# RPI.net
KiCad netlist of a schematic drawn in Altium Designer
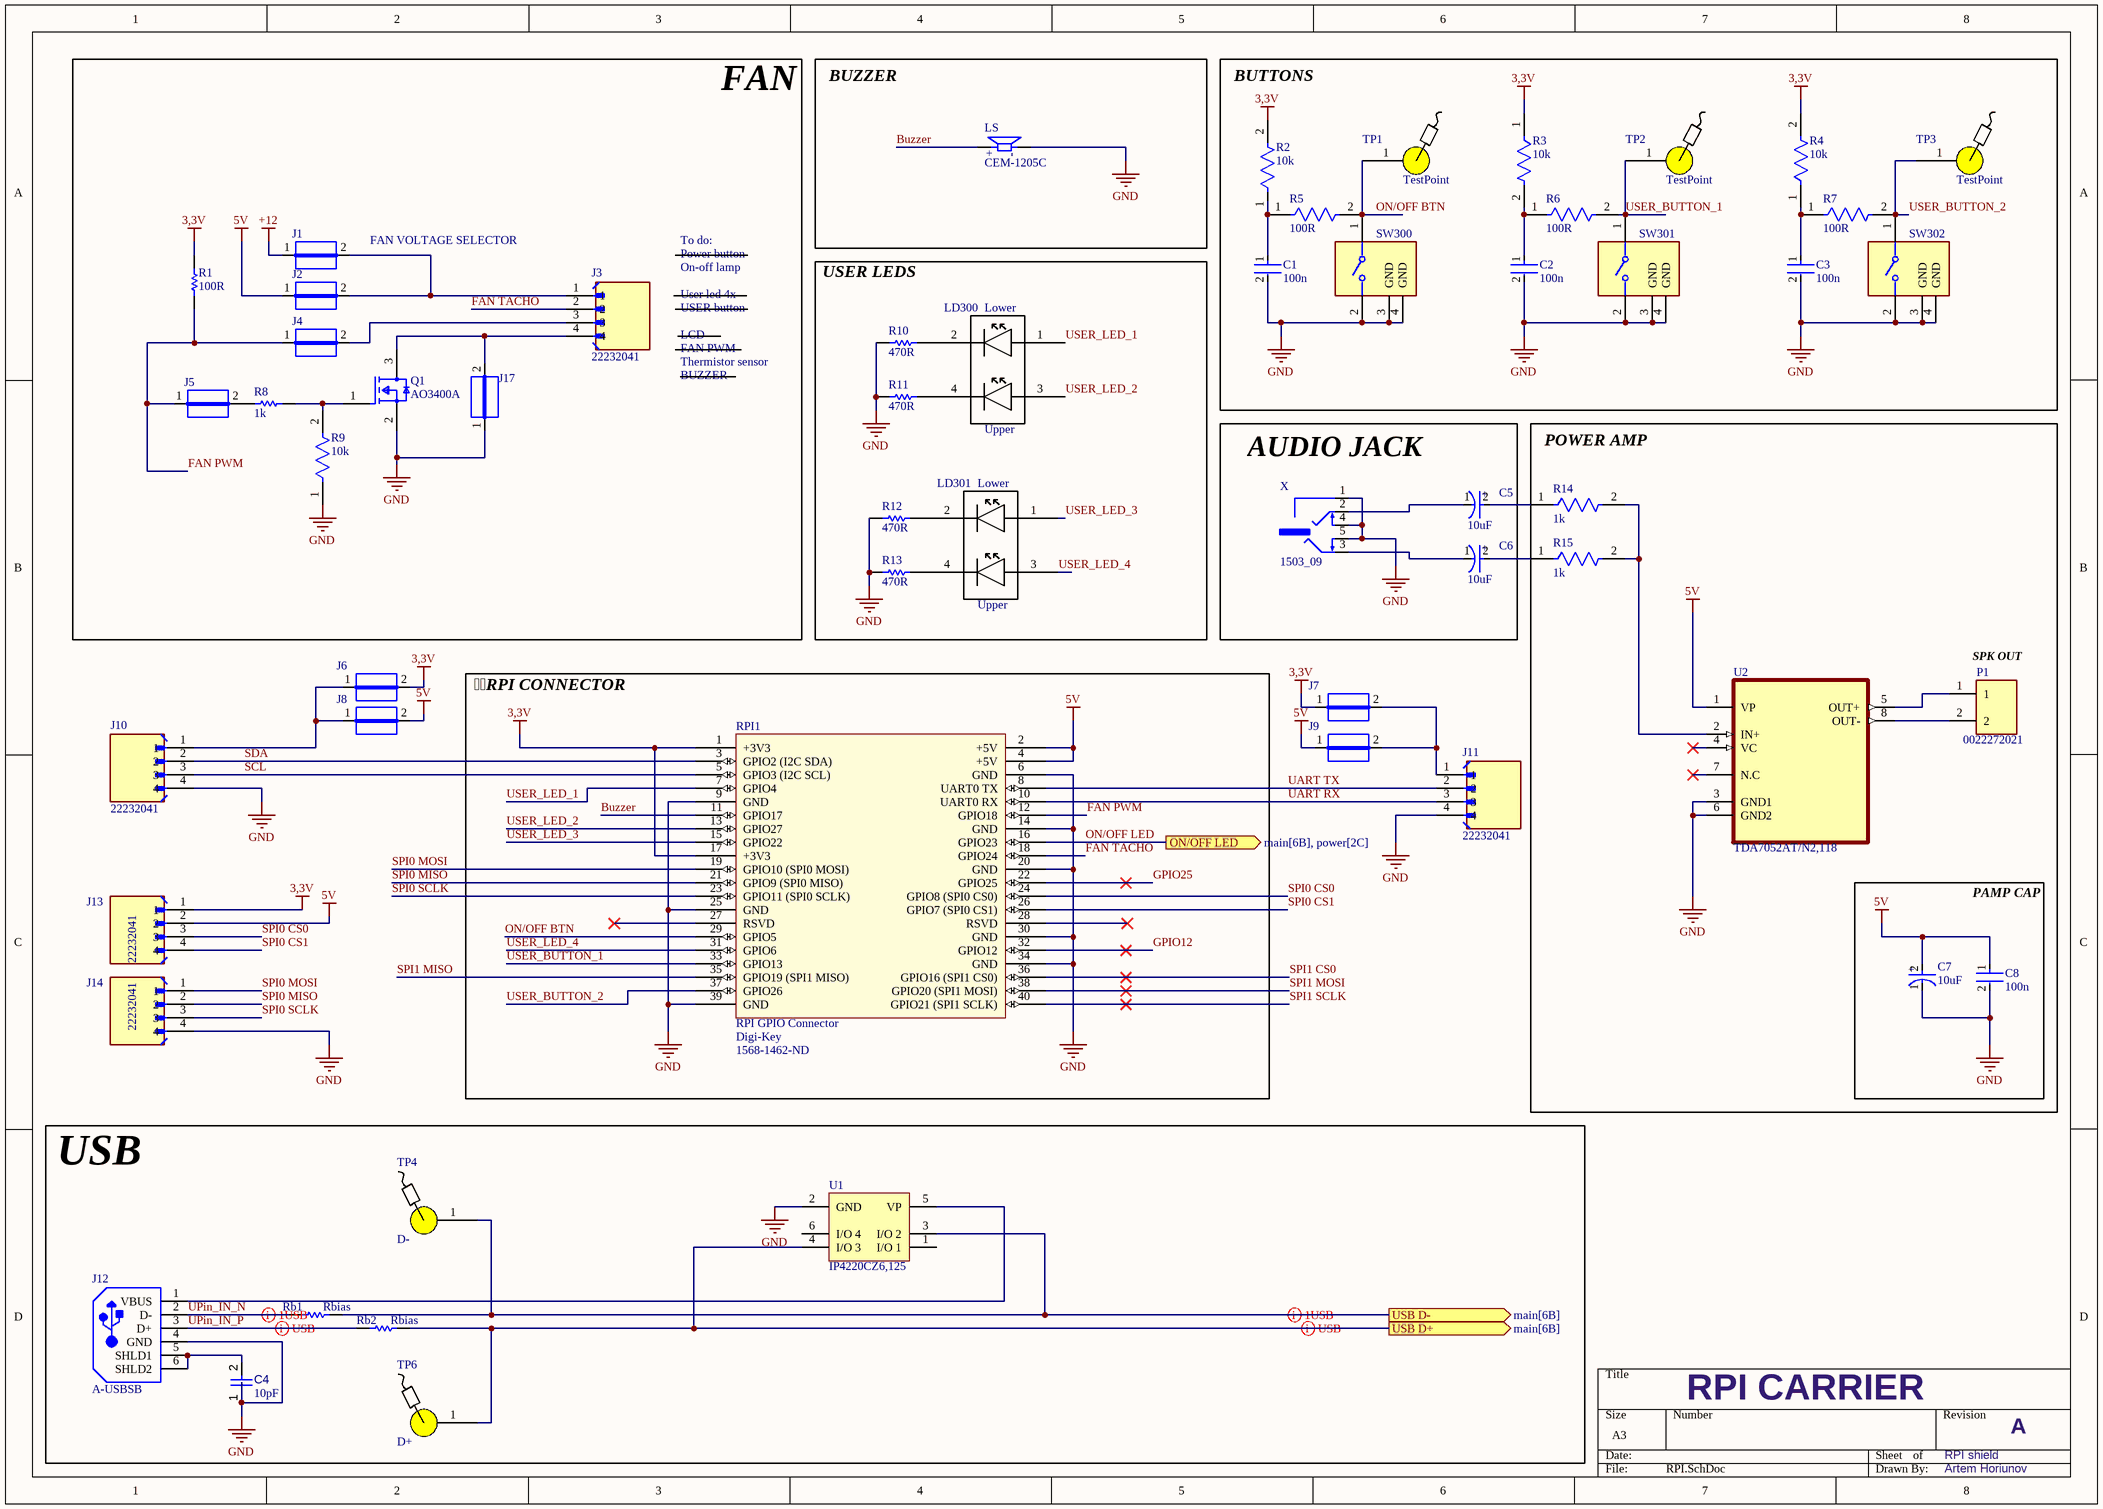
[diagram p0: RPI.SchDoc]

(export (version "E")
  (design (tool "Eeschema 10.0.6"))
  (components
    (comp (ref "C1")
      (value "100n")
      (footprint "FP-C0603C-CF-MFG")
      (description "CAP CER 0.1UF 50V X7R 0603")
      (fields (field (name "TOLERANCE") "0.1") (field (name "MANUFACTURER") "KEMET"))
      (libsource (lib "Altium Content Vault") (part "b4654b650e69147ec39a6b967a45e02"))
    )
    (comp (ref "C2")
      (value "100n")
      (footprint "FP-C0603C-CF-MFG")
      (description "CAP CER 0.1UF 50V X7R 0603")
      (fields (field (name "TOLERANCE") "0.1") (field (name "MANUFACTURER") "KEMET"))
      (libsource (lib "Altium Content Vault") (part "b4654b650e69147ec39a6b967a45e02"))
    )
    (comp (ref "C3")
      (value "100n")
      (footprint "FP-C0603C-CF-MFG")
      (description "CAP CER 0.1UF 50V X7R 0603")
      (fields (field (name "TOLERANCE") "0.1") (field (name "MANUFACTURER") "KEMET"))
      (libsource (lib "Altium Content Vault") (part "b4654b650e69147ec39a6b967a45e02"))
    )
    (comp (ref "C4")
      (value "10pF")
      (footprint "CAPC1005X55X30LL05T10")
      (description "Chip Capacitor, 10 pF, +/- 0.25 pF, 50 V, 0402 (1005 Metric)")
      (fields
        (field (name "TOLERANCE") "0.25%")
        (field (name "Comment") "Capacitor 10 pF +/- 0.25 pF 50 V 0402")
      )
      (libsource (lib "WUST") (part "CAP-NP-2"))
    )
    (comp (ref "C5")
      (value "10uF")
      (footprint "FP-SC-MFG")
      (description "CAP ALUM 10UF 20% 35V SMD")
      (fields (field (name "TOLERANCE") "20%") (field (name "VOLTAGE") "35V"))
      (libsource (lib "Altium Content Vault") (part "203bc49f2ac43e59fd269a8c329ed05"))
    )
    (comp (ref "C6")
      (value "10uF")
      (footprint "FP-SC-MFG")
      (description "CAP ALUM 10UF 20% 35V SMD")
      (fields (field (name "TOLERANCE") "20%") (field (name "VOLTAGE") "35V"))
      (libsource (lib "Altium Content Vault") (part "203bc49f2ac43e59fd269a8c329ed05"))
    )
    (comp (ref "C7")
      (value "10uF")
      (footprint "FP-SC-MFG")
      (description "CAP ALUM 10UF 20% 35V SMD")
      (fields (field (name "TOLERANCE") "20%") (field (name "VOLTAGE") "35V"))
      (libsource (lib "Altium Content Vault") (part "203bc49f2ac43e59fd269a8c329ed05"))
    )
    (comp (ref "C8")
      (value "100n")
      (footprint "FP-C0603C-CF-MFG")
      (description "CAP CER 0.1UF 50V X7R 0603")
      (fields (field (name "TOLERANCE") "0.1") (field (name "MANUFACTURER") "KEMET"))
      (libsource (lib "Altium Content Vault") (part "b4654b650e69147ec39a6b967a45e02"))
    )
    (comp (ref "J1") (value "JUMPER") (footprint "JUMPER") (libsource (lib "") (part "JUMPER_1")))
    (comp (ref "J2") (value "JUMPER") (footprint "JUMPER") (libsource (lib "") (part "JUMPER_1")))
    (comp (ref "J3")
      (value "22232041")
      (footprint "MOLEX_22232041")
      (description "Conn Wire to Board HDR 4 POS 2.54mm Solder ST Top Entry Thru-Hole KKÂ® Bag")
      (fields (field (name "MF") "Molex"))
      (libsource (lib "22232041") (part "22232041"))
    )
    (comp (ref "J4") (value "JUMPER") (footprint "JUMPER") (libsource (lib "") (part "JUMPER_1")))
    (comp (ref "J5") (value "JUMPER") (footprint "JUMPER") (libsource (lib "") (part "JUMPER_1")))
    (comp (ref "J6") (value "JUMPER") (footprint "JUMPER") (libsource (lib "") (part "JUMPER_1")))
    (comp (ref "J7") (value "JUMPER") (footprint "JUMPER") (libsource (lib "") (part "JUMPER_1")))
    (comp (ref "J8") (value "JUMPER") (footprint "JUMPER") (libsource (lib "") (part "JUMPER_1")))
    (comp (ref "J9") (value "JUMPER") (footprint "JUMPER") (libsource (lib "") (part "JUMPER_1")))
    (comp (ref "J10")
      (value "22232041")
      (footprint "MOLEX_22232041")
      (description "Conn Wire to Board HDR 4 POS 2.54mm Solder ST Top Entry Thru-Hole KKÂ® Bag")
      (fields (field (name "MF") "Molex"))
      (libsource (lib "") (part "22232041_1"))
    )
    (comp (ref "J11")
      (value "22232041")
      (footprint "MOLEX_22232041")
      (description "Conn Wire to Board HDR 4 POS 2.54mm Solder ST Top Entry Thru-Hole KKÂ® Bag")
      (fields (field (name "MF") "Molex"))
      (libsource (lib "22232041") (part "22232041"))
    )
    (comp (ref "J12")
      (value "A-USBSB")
      (footprint "ASSM-A-USBSB-4_V")
      (description "Connector Receptacle, USB Type B, Right Angle, -20 to 85 degC, 4-Pin THD, RoHS, Tray")
      (fields (field (name "MANUFACTURER") "ASSMANN WSW"))
      (libsource (lib "Altium Content Vault") (part "USB-4-2SHLD"))
    )
    (comp (ref "J13")
      (value "22232041")
      (footprint "MOLEX_22232041")
      (description "Conn Wire to Board HDR 4 POS 2.54mm Solder ST Top Entry Thru-Hole KKÂ® Bag")
      (fields (field (name "MF") "Molex"))
      (libsource (lib "") (part "22232041_2"))
    )
    (comp (ref "J14")
      (value "22232041")
      (footprint "MOLEX_22232041")
      (description "Conn Wire to Board HDR 4 POS 2.54mm Solder ST Top Entry Thru-Hole KKÂ® Bag")
      (fields (field (name "MF") "Molex"))
      (libsource (lib "") (part "22232041_2"))
    )
    (comp (ref "J17") (value "JUMPER") (footprint "JUMPER") (libsource (lib "WUST") (part "JUMPER")))
    (comp (ref "LD300")
      (value "~")
      (footprint "LedHolder:LED_HOLDER")
      (libsource (lib "LedHolder") (part "DoubleStack_Side_Led_3mm"))
    )
    (comp (ref "LD301")
      (value "~")
      (footprint "LedHolder:LED_HOLDER")
      (libsource (lib "LedHolder") (part "DoubleStack_Side_Led_3mm"))
    )
    (comp (ref "LS")
      (value "CEM-1205C")
      (footprint "CUI_CEM-1205C")
      (description "12 mm, 5 V, 85 dB, Through Hole, Sealed, Driving Circuit, Magnetic Audio Indicator Buzzer")
      (fields (field (name "MF") "CUI Devices"))
      (libsource (lib "CEM-1205C") (part "CEM-1205C"))
    )
    (comp (ref "P1")
      (value "0022272021")
      (footprint "MOLEX_0022272021")
      (description "Connector Header Through Hole 2 position 0.100 (2.54mm)")
      (fields (field (name "MF") "Molex"))
      (libsource (lib "0022272021") (part "0022272021"))
    )
    (comp (ref "Q1")
      (value "AO3400A")
      (footprint "FP-SOT23-MFG")
      (description "MOSFET N-CH 30V 5.7A SOT23")
      (libsource (lib "Altium Content Vault") (part "0a9ea7c96deaaede766a5b531c28de0"))
    )
    (comp (ref "R1")
      (value "100R")
      (footprint "RESC0603(1608)_N")
      (description "0.1W 1% 0603 (1608 Metric)  SMD")
      (fields (field (name "TOLERANCE") "5 %") (field (name "POWER") "0.1 W"))
      (libsource (lib "Altium Content Vault") (part "RES"))
    )
    (comp (ref "R2")
      (value "10k")
      (footprint "FP-RC0603-0_55-IPC_C")
      (description "RES 10K OHM 1% 1/10W 0603")
      (fields (field (name "TOLERANCE") "1%"))
      (libsource (lib "Altium Content Vault") (part "1029c3af85768c4190bb7ad29bc67b5"))
    )
    (comp (ref "R3")
      (value "10k")
      (footprint "FP-RC0603-0_55-IPC_C")
      (description "RES 10K OHM 1% 1/10W 0603")
      (fields (field (name "TOLERANCE") "1%"))
      (libsource (lib "Altium Content Vault") (part "1029c3af85768c4190bb7ad29bc67b5"))
    )
    (comp (ref "R4")
      (value "10k")
      (footprint "FP-RC0603-0_55-IPC_C")
      (description "RES 10K OHM 1% 1/10W 0603")
      (fields (field (name "TOLERANCE") "1%"))
      (libsource (lib "Altium Content Vault") (part "1029c3af85768c4190bb7ad29bc67b5"))
    )
    (comp (ref "R5")
      (value "100R")
      (footprint "FP-RC0603-0_55-MFG")
      (fields (field (name "TOLERANCE") "1%"))
      (libsource (lib "Altium Content Vault") (part "1029c3af85768c4190bb7ad29bc67b5"))
    )
    (comp (ref "R6")
      (value "100R")
      (footprint "FP-RC0603-0_55-MFG")
      (fields (field (name "TOLERANCE") "1%"))
      (libsource (lib "Altium Content Vault") (part "1029c3af85768c4190bb7ad29bc67b5"))
    )
    (comp (ref "R7")
      (value "100R")
      (footprint "FP-RC0603-0_55-MFG")
      (fields (field (name "TOLERANCE") "1%"))
      (libsource (lib "Altium Content Vault") (part "1029c3af85768c4190bb7ad29bc67b5"))
    )
    (comp (ref "R8")
      (value "1k")
      (footprint "RESC0603(1608)_N")
      (description "0.1W 5% 0603 (1608 Metric)  SMD")
      (fields (field (name "TOLERANCE") "5 %") (field (name "POWER") "0.1 W"))
      (libsource (lib "Altium Content Vault") (part "RES"))
    )
    (comp (ref "R9")
      (value "10k")
      (footprint "FP-RC0603-0_55-IPC_C")
      (description "RES 10K OHM 1% 1/10W 0603")
      (fields (field (name "TOLERANCE") "1%"))
      (libsource (lib "Altium Content Vault") (part "1029c3af85768c4190bb7ad29bc67b5"))
    )
    (comp (ref "R10")
      (value "470R")
      (footprint "RESC1608X55X25LL10T15")
      (libsource (lib "Altium Content Vault") (part "RES-2"))
    )
    (comp (ref "R11")
      (value "470R")
      (footprint "RESC1608X55X25LL10T15")
      (libsource (lib "Altium Content Vault") (part "RES-2"))
    )
    (comp (ref "R12")
      (value "470R")
      (footprint "RESC1608X55X25LL10T15")
      (libsource (lib "Altium Content Vault") (part "RES-2"))
    )
    (comp (ref "R13")
      (value "470R")
      (footprint "RESC1608X55X25LL10T15")
      (libsource (lib "Altium Content Vault") (part "RES-2"))
    )
    (comp (ref "R14")
      (value "1k")
      (footprint "FP-ERA3A-IPC_C")
      (description "RES SMD 1K OHM 0.1% 1/10W 0603")
      (fields (field (name "TOLERANCE") "0.1%"))
      (libsource (lib "Altium Content Vault") (part "1029c3af85768c4190bb7ad29bc67b5"))
    )
    (comp (ref "R15")
      (value "1k")
      (footprint "FP-ERA3A-IPC_C")
      (description "RES SMD 1K OHM 0.1% 1/10W 0603")
      (fields (field (name "TOLERANCE") "0.1%"))
      (libsource (lib "Altium Content Vault") (part "1029c3af85768c4190bb7ad29bc67b5"))
    )
    (comp (ref "Rb1")
      (value "Rbias")
      (footprint "RESC1005X40X25NL05T05")
      (fields (field (name "PART NUMBER") "CRCW040210R0FKED") (field (name "MANUFACTURER") "Vishay Dale"))
      (libsource (lib "Altium Content Vault") (part "RES"))
    )
    (comp (ref "Rb2")
      (value "Rbias")
      (footprint "RESC1005X40X25NL05T05")
      (fields (field (name "PART NUMBER") "CRCW040210R0FKED") (field (name "MANUFACTURER") "Vishay Dale"))
      (libsource (lib "Altium Content Vault") (part "RES"))
    )
    (comp (ref "RPI1")
      (value "RPI GPIO Connector")
      (footprint "rpi")
      (description "GPIO Header for Raspberry Pi A+/B+/Pi 2/Pi 3 - 2x20")
      (fields
        (field (name "MANUFACTURER") "SparkFun Electronics")
        (field (name "MANUFACTURER PART NUMBER") "PRT-14017")
        (field (name "SUPPLIER 1") "Digi-Key")
        (field (name "SUPPLIER PART NUMBER 1") "1568-1462-ND")
      )
      (libsource (lib "rpi") (part "rpi connector"))
    )
    (comp (ref "SW300")
      (value "B3F-3122")
      (footprint "FP-B3F-3122-MFG")
      (description "SWITCH TACTILE SPST-NO 0.05A 24V")
      (libsource (lib "Altium Content Vault") (part "05c531d4b500f7e9514fa3f65f375ae"))
    )
    (comp (ref "SW301")
      (value "B3F-3122")
      (footprint "FP-B3F-3122-MFG")
      (description "SWITCH TACTILE SPST-NO 0.05A 24V")
      (libsource (lib "Altium Content Vault") (part "05c531d4b500f7e9514fa3f65f375ae"))
    )
    (comp (ref "SW302")
      (value "B3F-3122")
      (footprint "FP-B3F-3122-MFG")
      (description "SWITCH TACTILE SPST-NO 0.05A 24V")
      (libsource (lib "Altium Content Vault") (part "05c531d4b500f7e9514fa3f65f375ae"))
    )
    (comp (ref "TP1")
      (value "TestPoint")
      (footprint "TestPoint")
      (libsource (lib "TestPoint") (part "TestPoint"))
    )
    (comp (ref "TP2")
      (value "TestPoint")
      (footprint "TestPoint")
      (libsource (lib "TestPoint") (part "TestPoint"))
    )
    (comp (ref "TP3")
      (value "TestPoint")
      (footprint "TestPoint")
      (libsource (lib "TestPoint") (part "TestPoint"))
    )
    (comp (ref "TP4") (value "D-") (footprint "TestPoint") (libsource (lib "TestPoint") (part "TestPoint")))
    (comp (ref "TP6") (value "D+") (footprint "TestPoint") (libsource (lib "TestPoint") (part "TestPoint")))
    (comp (ref "U1")
      (value "IP4220CZ6,125")
      (footprint "NXP-SOT457_L")
      (fields (field (name "PARTNUMBER") "IP4220CZ6") (field (name "MANUFACTURER") "NXP Semiconductors"))
      (libsource (lib "Altium Content Vault") (part "NXP-IP4220CZ6-6"))
    )
    (comp (ref "U2")
      (value "TDA7052AT/N2,118")
      (footprint "SOIC127P600X175-8N")
      (description "1 W BTL mono audio amplifier with DC volume control")
      (libsource (lib "TDA7052AT_N2_118") (part "TDA7052AT/N2,118"))
    )
    (comp (ref "X")
      (value "1503_09")
      (footprint "1503_09")
      (description "1503 - Lumberg 3.5mm Right Angle Jack Chassis Socket")
      (fields (field (name "MP") "1503 09") (field (name "MF") "NEC"))
      (libsource (lib "1503_09") (part "1503_09"))
    )
  )
  (nets
    (net (code "1") (name "+12") (class "Default")
      (node (ref "J1") (pin "1") (pinfunction "1_1") (pintype "passive"))
    )
    (net (code "2") (name "/Buzzer") (class "Default")
      (node (ref "LS") (pin "P") (pinfunction "P_P") (pintype "passive"))
      (node (ref "RPI1") (pin "11") (pinfunction "GPIO17_11") (pintype "bidirectional"))
    )
    (net (code "3") (name "/FAN PWM") (class "Default")
      (node (ref "J4") (pin "1") (pinfunction "1_1") (pintype "passive"))
      (node (ref "J5") (pin "1") (pinfunction "1_1") (pintype "passive"))
      (node (ref "R1") (pin "1") (pinfunction "1_1") (pintype "passive"))
      (node (ref "RPI1") (pin "12") (pinfunction "GPIO18_12") (pintype "bidirectional"))
    )
    (net (code "4") (name "/FAN TACHO") (class "Default")
      (node (ref "J3") (pin "2") (pinfunction "2_2") (pintype "passive"))
      (node (ref "RPI1") (pin "18") (pinfunction "GPIO24_18") (pintype "bidirectional"))
    )
    (net (code "5") (name "/GPIO12") (class "Default")
      (node (ref "RPI1") (pin "32") (pinfunction "GPIO12_32") (pintype "bidirectional"))
    )
    (net (code "6") (name "/GPIO25") (class "Default")
      (node (ref "RPI1") (pin "22") (pinfunction "GPIO25_22") (pintype "bidirectional"))
    )
    (net (code "7") (name "/ON{slash}OFF BTN") (class "Default")
      (node (ref "R5") (pin "2") (pinfunction "2_2") (pintype "passive"))
      (node (ref "RPI1") (pin "29") (pinfunction "GPIO5_29") (pintype "bidirectional"))
      (node (ref "SW300") (pin "1") (pinfunction "1_1") (pintype "passive"))
      (node (ref "TP1") (pin "1") (pintype "passive"))
    )
    (net (code "8") (name "/ON{slash}OFF LED") (class "Default")
      (node (ref "RPI1") (pin "16") (pinfunction "GPIO23_16") (pintype "bidirectional"))
    )
    (net (code "9") (name "/SCL") (class "Default")
      (node (ref "J10") (pin "3") (pinfunction "3_3") (pintype "passive"))
      (node (ref "RPI1") (pin "5") (pinfunction "GPIO3_(I2C_SCL)_5") (pintype "bidirectional"))
    )
    (net (code "10") (name "/SDA") (class "Default")
      (node (ref "J10") (pin "2") (pinfunction "2_2") (pintype "passive"))
      (node (ref "RPI1") (pin "3") (pinfunction "GPIO2_(I2C_SDA)_3") (pintype "bidirectional"))
    )
    (net (code "11") (name "/SPI0 CS0") (class "Default")
      (node (ref "J13") (pin "3") (pinfunction "3_3") (pintype "passive"))
      (node (ref "RPI1") (pin "24") (pinfunction "GPIO8_(SPI0_CS0)_24") (pintype "bidirectional"))
    )
    (net (code "12") (name "/SPI0 CS1") (class "Default")
      (node (ref "J13") (pin "4") (pinfunction "4_4") (pintype "passive"))
      (node (ref "RPI1") (pin "26") (pinfunction "GPIO7_(SPI0_CS1)_26") (pintype "bidirectional"))
    )
    (net (code "13") (name "/SPI0 MISO") (class "Default")
      (node (ref "J14") (pin "2") (pinfunction "2_2") (pintype "passive"))
      (node (ref "RPI1") (pin "21") (pinfunction "GPIO9_(SPI0_MISO)_21") (pintype "bidirectional"))
    )
    (net (code "14") (name "/SPI0 MOSI") (class "Default")
      (node (ref "J14") (pin "1") (pinfunction "1_1") (pintype "passive"))
      (node (ref "RPI1") (pin "19") (pinfunction "GPIO10_(SPI0_MOSI)_19") (pintype "bidirectional"))
    )
    (net (code "15") (name "/SPI0 SCLK") (class "Default")
      (node (ref "J14") (pin "3") (pinfunction "3_3") (pintype "passive"))
      (node (ref "RPI1") (pin "23") (pinfunction "GPIO11_(SPI0_SCLK)_23") (pintype "bidirectional"))
    )
    (net (code "16") (name "/SPI1 CS0") (class "Default")
      (node (ref "RPI1") (pin "36") (pinfunction "GPIO16_(SPI1_CS0)_36") (pintype "bidirectional"))
    )
    (net (code "17") (name "/SPI1 MISO") (class "Default")
      (node (ref "RPI1") (pin "35") (pinfunction "GPIO19_(SPI1_MISO)_35") (pintype "bidirectional"))
    )
    (net (code "18") (name "/SPI1 MOSI") (class "Default")
      (node (ref "RPI1") (pin "38") (pinfunction "GPIO20_(SPI1_MOSI)_38") (pintype "bidirectional"))
    )
    (net (code "19") (name "/SPI1 SCLK") (class "Default")
      (node (ref "RPI1") (pin "40") (pinfunction "GPIO21_(SPI1_SCLK)_40") (pintype "bidirectional"))
    )
    (net (code "20") (name "/UART RX") (class "Default")
      (node (ref "J11") (pin "3") (pinfunction "3_3") (pintype "passive"))
      (node (ref "RPI1") (pin "10") (pinfunction "UART0_RX_10") (pintype "bidirectional"))
    )
    (net (code "21") (name "/UART TX") (class "Default")
      (node (ref "J11") (pin "2") (pinfunction "2_2") (pintype "passive"))
      (node (ref "RPI1") (pin "8") (pinfunction "UART0_TX_8") (pintype "bidirectional"))
    )
    (net (code "22") (name "/UPin_IN_N") (class "Default")
      (node (ref "J12") (pin "2") (pinfunction "D-_2") (pintype "passive"))
      (node (ref "Rb1") (pin "1") (pinfunction "1_1") (pintype "passive"))
    )
    (net (code "23") (name "/UPin_IN_P") (class "Default")
      (node (ref "J12") (pin "3") (pinfunction "D+_3") (pintype "passive"))
      (node (ref "Rb2") (pin "1") (pinfunction "1_1") (pintype "passive"))
    )
    (net (code "24") (name "/USB D+") (class "Default")
      (node (ref "Rb2") (pin "2") (pinfunction "2_2") (pintype "passive"))
      (node (ref "TP6") (pin "1") (pintype "passive"))
      (node (ref "U1") (pin "4") (pinfunction "I/O_3_4") (pintype "passive"))
    )
    (net (code "25") (name "/USB D-") (class "Default")
      (node (ref "Rb1") (pin "2") (pinfunction "2_2") (pintype "passive"))
      (node (ref "TP4") (pin "1") (pintype "passive"))
      (node (ref "U1") (pin "3") (pinfunction "I/O_2_3") (pintype "passive"))
    )
    (net (code "26") (name "/USER_BUTTON_1") (class "Default")
      (node (ref "R6") (pin "2") (pinfunction "2_2") (pintype "passive"))
      (node (ref "RPI1") (pin "33") (pinfunction "GPIO13_33") (pintype "bidirectional"))
      (node (ref "SW301") (pin "1") (pinfunction "1_1") (pintype "passive"))
      (node (ref "TP2") (pin "1") (pintype "passive"))
    )
    (net (code "27") (name "/USER_BUTTON_2") (class "Default")
      (node (ref "R7") (pin "2") (pinfunction "2_2") (pintype "passive"))
      (node (ref "RPI1") (pin "37") (pinfunction "GPIO26_37") (pintype "bidirectional"))
      (node (ref "SW302") (pin "1") (pinfunction "1_1") (pintype "passive"))
      (node (ref "TP3") (pin "1") (pintype "passive"))
    )
    (net (code "28") (name "/USER_LED_1") (class "Default")
      (node (ref "LD300") (pin "1") (pintype "passive"))
      (node (ref "RPI1") (pin "7") (pinfunction "GPIO4_7") (pintype "bidirectional"))
    )
    (net (code "29") (name "/USER_LED_2") (class "Default")
      (node (ref "LD300") (pin "3") (pintype "passive"))
      (node (ref "RPI1") (pin "13") (pinfunction "GPIO27_13") (pintype "bidirectional"))
    )
    (net (code "30") (name "/USER_LED_3") (class "Default")
      (node (ref "LD301") (pin "1") (pintype "passive"))
      (node (ref "RPI1") (pin "15") (pinfunction "GPIO22_15") (pintype "bidirectional"))
    )
    (net (code "31") (name "/USER_LED_4") (class "Default")
      (node (ref "LD301") (pin "3") (pintype "passive"))
      (node (ref "RPI1") (pin "31") (pinfunction "GPIO6_31") (pintype "bidirectional"))
    )
    (net (code "32") (name "3,3V") (class "Default")
      (node (ref "J13") (pin "1") (pinfunction "1_1") (pintype "passive"))
      (node (ref "J6") (pin "2") (pinfunction "2_2") (pintype "passive"))
      (node (ref "J7") (pin "1") (pinfunction "1_1") (pintype "passive"))
      (node (ref "R1") (pin "2") (pinfunction "2_2") (pintype "passive"))
      (node (ref "R2") (pin "2") (pinfunction "2_2") (pintype "passive"))
      (node (ref "R3") (pin "1") (pinfunction "1_1") (pintype "passive"))
      (node (ref "R4") (pin "2") (pinfunction "2_2") (pintype "passive"))
      (node (ref "RPI1") (pin "1") (pinfunction "+3V3_1") (pintype "power_in"))
      (node (ref "RPI1") (pin "17") (pinfunction "+3V3_17") (pintype "power_in"))
    )
    (net (code "33") (name "5V") (class "Default")
      (node (ref "C7") (pin "2") (pinfunction "A_2") (pintype "passive"))
      (node (ref "C8") (pin "1") (pinfunction "1_1") (pintype "passive"))
      (node (ref "J13") (pin "2") (pinfunction "2_2") (pintype "passive"))
      (node (ref "J2") (pin "1") (pinfunction "1_1") (pintype "passive"))
      (node (ref "J8") (pin "2") (pinfunction "2_2") (pintype "passive"))
      (node (ref "J9") (pin "1") (pinfunction "1_1") (pintype "passive"))
      (node (ref "RPI1") (pin "2") (pinfunction "+5V_2") (pintype "power_in"))
      (node (ref "RPI1") (pin "4") (pinfunction "+5V_4") (pintype "power_in"))
      (node (ref "U2") (pin "1") (pinfunction "VP_1") (pintype "power_in"))
    )
    (net (code "34") (name "GND") (class "Default")
      (node (ref "C1") (pin "2") (pinfunction "2_2") (pintype "passive"))
      (node (ref "C2") (pin "2") (pinfunction "2_2") (pintype "passive"))
      (node (ref "C3") (pin "2") (pinfunction "2_2") (pintype "passive"))
      (node (ref "C4") (pin "1") (pinfunction "1_1") (pintype "passive"))
      (node (ref "C7") (pin "1") (pinfunction "C_1") (pintype "passive"))
      (node (ref "C8") (pin "2") (pinfunction "2_2") (pintype "passive"))
      (node (ref "J10") (pin "4") (pinfunction "4_4") (pintype "passive"))
      (node (ref "J11") (pin "4") (pinfunction "4_4") (pintype "passive"))
      (node (ref "J12") (pin "4") (pinfunction "GND_4") (pintype "passive"))
      (node (ref "J14") (pin "4") (pinfunction "4_4") (pintype "passive"))
      (node (ref "J17") (pin "1") (pinfunction "1_1") (pintype "passive"))
      (node (ref "LS") (pin "N") (pinfunction "N_N") (pintype "passive"))
      (node (ref "Q1") (pin "2") (pinfunction "S_2") (pintype "passive"))
      (node (ref "R10") (pin "1") (pinfunction "1_1") (pintype "passive"))
      (node (ref "R11") (pin "1") (pinfunction "1_1") (pintype "passive"))
      (node (ref "R12") (pin "1") (pinfunction "1_1") (pintype "passive"))
      (node (ref "R13") (pin "1") (pinfunction "1_1") (pintype "passive"))
      (node (ref "R9") (pin "1") (pinfunction "1_1") (pintype "passive"))
      (node (ref "RPI1") (pin "14") (pinfunction "GND_14") (pintype "power_in"))
      (node (ref "RPI1") (pin "20") (pinfunction "GND_20") (pintype "power_in"))
      (node (ref "RPI1") (pin "25") (pinfunction "GND_25") (pintype "power_in"))
      (node (ref "RPI1") (pin "30") (pinfunction "GND_30") (pintype "power_in"))
      (node (ref "RPI1") (pin "34") (pinfunction "GND_34") (pintype "passive"))
      (node (ref "RPI1") (pin "39") (pinfunction "GND_39") (pintype "power_in"))
      (node (ref "RPI1") (pin "6") (pinfunction "GND_6") (pintype "power_in"))
      (node (ref "RPI1") (pin "9") (pinfunction "GND_9") (pintype "power_in"))
      (node (ref "SW300") (pin "2") (pinfunction "2_2") (pintype "passive"))
      (node (ref "SW300") (pin "3") (pinfunction "GND_3") (pintype "power_in"))
      (node (ref "SW300") (pin "4") (pinfunction "GND_4") (pintype "power_in"))
      (node (ref "SW301") (pin "2") (pinfunction "2_2") (pintype "passive"))
      (node (ref "SW301") (pin "3") (pinfunction "GND_3") (pintype "power_in"))
      (node (ref "SW301") (pin "4") (pinfunction "GND_4") (pintype "power_in"))
      (node (ref "SW302") (pin "2") (pinfunction "2_2") (pintype "passive"))
      (node (ref "SW302") (pin "3") (pinfunction "GND_3") (pintype "power_in"))
      (node (ref "SW302") (pin "4") (pinfunction "GND_4") (pintype "power_in"))
      (node (ref "U1") (pin "2") (pinfunction "GND_2") (pintype "power_in"))
      (node (ref "U2") (pin "3") (pinfunction "GND1_3") (pintype "passive"))
      (node (ref "U2") (pin "6") (pinfunction "GND2_6") (pintype "passive"))
      (node (ref "X") (pin "1") (pinfunction "1_1") (pintype "passive"))
      (node (ref "X") (pin "4") (pinfunction "4_4") (pintype "passive"))
      (node (ref "X") (pin "5") (pinfunction "5_5") (pintype "passive"))
    )
    (net (code "35") (name "Net-(C1-Pad1)") (class "Default")
      (node (ref "C1") (pin "1") (pinfunction "1_1") (pintype "passive"))
      (node (ref "R2") (pin "1") (pinfunction "1_1") (pintype "passive"))
      (node (ref "R5") (pin "1") (pinfunction "1_1") (pintype "passive"))
    )
    (net (code "36") (name "Net-(C2-Pad1)") (class "Default")
      (node (ref "C2") (pin "1") (pinfunction "1_1") (pintype "passive"))
      (node (ref "R3") (pin "2") (pinfunction "2_2") (pintype "passive"))
      (node (ref "R6") (pin "1") (pinfunction "1_1") (pintype "passive"))
    )
    (net (code "37") (name "Net-(C3-Pad1)") (class "Default")
      (node (ref "C3") (pin "1") (pinfunction "1_1") (pintype "passive"))
      (node (ref "R4") (pin "1") (pinfunction "1_1") (pintype "passive"))
      (node (ref "R7") (pin "1") (pinfunction "1_1") (pintype "passive"))
    )
    (net (code "38") (name "Net-(C5-A)") (class "Default")
      (node (ref "C5") (pin "2") (pinfunction "A_2") (pintype "passive"))
      (node (ref "R14") (pin "1") (pinfunction "1_1") (pintype "passive"))
    )
    (net (code "39") (name "Net-(C5-C)") (class "Default")
      (node (ref "C5") (pin "1") (pinfunction "C_1") (pintype "passive"))
      (node (ref "X") (pin "2") (pinfunction "2_2") (pintype "passive"))
    )
    (net (code "40") (name "Net-(C6-A)") (class "Default")
      (node (ref "C6") (pin "2") (pinfunction "A_2") (pintype "passive"))
      (node (ref "R15") (pin "1") (pinfunction "1_1") (pintype "passive"))
    )
    (net (code "41") (name "Net-(C6-C)") (class "Default")
      (node (ref "C6") (pin "1") (pinfunction "C_1") (pintype "passive"))
      (node (ref "X") (pin "3") (pinfunction "3_3") (pintype "passive"))
    )
    (net (code "42") (name "Net-(J1-Pad2)") (class "Default")
      (node (ref "J1") (pin "2") (pinfunction "2_2") (pintype "passive"))
      (node (ref "J2") (pin "2") (pinfunction "2_2") (pintype "passive"))
      (node (ref "J3") (pin "1") (pinfunction "1_1") (pintype "passive"))
    )
    (net (code "43") (name "Net-(J3-Pad3)") (class "Default")
      (node (ref "J3") (pin "3") (pinfunction "3_3") (pintype "passive"))
      (node (ref "J4") (pin "2") (pinfunction "2_2") (pintype "passive"))
    )
    (net (code "44") (name "Net-(J5-Pad2)") (class "Default")
      (node (ref "J5") (pin "2") (pinfunction "2_2") (pintype "passive"))
      (node (ref "R8") (pin "2") (pinfunction "2_2") (pintype "passive"))
    )
    (net (code "45") (name "Net-(J10-Pad1)") (class "Default")
      (node (ref "J10") (pin "1") (pinfunction "1_1") (pintype "passive"))
      (node (ref "J6") (pin "1") (pinfunction "1_1") (pintype "passive"))
      (node (ref "J8") (pin "1") (pinfunction "1_1") (pintype "passive"))
    )
    (net (code "46") (name "Net-(J11-Pad1)") (class "Default")
      (node (ref "J11") (pin "1") (pinfunction "1_1") (pintype "passive"))
      (node (ref "J7") (pin "2") (pinfunction "2_2") (pintype "passive"))
      (node (ref "J9") (pin "2") (pinfunction "2_2") (pintype "passive"))
    )
    (net (code "47") (name "Net-(J12-SHLD1)") (class "Default")
      (node (ref "C4") (pin "2") (pinfunction "2_2") (pintype "passive"))
      (node (ref "J12") (pin "5") (pinfunction "SHLD1_5") (pintype "passive"))
      (node (ref "J12") (pin "6") (pinfunction "SHLD2_6") (pintype "passive"))
    )
    (net (code "48") (name "Net-(J12-VBUS)") (class "Default")
      (node (ref "J12") (pin "1") (pinfunction "VBUS_1") (pintype "passive"))
      (node (ref "U1") (pin "5") (pinfunction "VP_5") (pintype "power_in"))
    )
    (net (code "49") (name "Net-(LD300-Pad2)") (class "Default")
      (node (ref "LD300") (pin "2") (pintype "passive"))
      (node (ref "R10") (pin "2") (pinfunction "2_2") (pintype "passive"))
    )
    (net (code "50") (name "Net-(LD300-Pad4)") (class "Default")
      (node (ref "LD300") (pin "4") (pintype "passive"))
      (node (ref "R11") (pin "2") (pinfunction "2_2") (pintype "passive"))
    )
    (net (code "51") (name "Net-(LD301-Pad2)") (class "Default")
      (node (ref "LD301") (pin "2") (pintype "passive"))
      (node (ref "R12") (pin "2") (pinfunction "2_2") (pintype "passive"))
    )
    (net (code "52") (name "Net-(LD301-Pad4)") (class "Default")
      (node (ref "LD301") (pin "4") (pintype "passive"))
      (node (ref "R13") (pin "2") (pinfunction "2_2") (pintype "passive"))
    )
    (net (code "53") (name "Net-(Q1-D)") (class "Default")
      (node (ref "J17") (pin "2") (pinfunction "2_2") (pintype "passive"))
      (node (ref "J3") (pin "4") (pinfunction "4_4") (pintype "passive"))
      (node (ref "Q1") (pin "3") (pinfunction "D_3") (pintype "passive"))
    )
    (net (code "54") (name "Net-(Q1-G)") (class "Default")
      (node (ref "Q1") (pin "1") (pinfunction "G_1") (pintype "passive"))
      (node (ref "R8") (pin "1") (pinfunction "1_1") (pintype "passive"))
      (node (ref "R9") (pin "2") (pinfunction "2_2") (pintype "passive"))
    )
    (net (code "55") (name "Net-(U2-IN+)") (class "Default")
      (node (ref "R14") (pin "2") (pinfunction "2_2") (pintype "passive"))
      (node (ref "R15") (pin "2") (pinfunction "2_2") (pintype "passive"))
      (node (ref "U2") (pin "2") (pinfunction "IN+_2") (pintype "input"))
    )
    (net (code "56") (name "Net-(U2-OUT+)") (class "Default")
      (node (ref "P1") (pin "1") (pinfunction "1_1") (pintype "passive"))
      (node (ref "U2") (pin "5") (pinfunction "OUT+_5") (pintype "output"))
    )
    (net (code "57") (name "Net-(U2-OUT-)") (class "Default")
      (node (ref "P1") (pin "2") (pinfunction "2_2") (pintype "passive"))
      (node (ref "U2") (pin "8") (pinfunction "OUT-_8") (pintype "output"))
    )
    (net (code "58") (name "unconnected-(RPI1-RSVD-Pad27)") (class "Default")
      (node (ref "RPI1") (pin "27") (pinfunction "RSVD_27") (pintype "passive+no_connect"))
    )
    (net (code "59") (name "unconnected-(RPI1-RSVD-Pad28)") (class "Default")
      (node (ref "RPI1") (pin "28") (pinfunction "RSVD_28") (pintype "passive+no_connect"))
    )
    (net (code "60") (name "unconnected-(U1-I{slash}O_1-Pad1)") (class "Default")
      (node (ref "U1") (pin "1") (pinfunction "I/O_1_1") (pintype "passive"))
    )
    (net (code "61") (name "unconnected-(U1-I{slash}O_4-Pad6)") (class "Default")
      (node (ref "U1") (pin "6") (pinfunction "I/O_4_6") (pintype "passive"))
    )
    (net (code "62") (name "unconnected-(U2-N.C-Pad7)") (class "Default")
      (node (ref "U2") (pin "7") (pinfunction "N.C_7") (pintype "passive+no_connect"))
    )
    (net (code "63") (name "unconnected-(U2-VC-Pad4)") (class "Default")
      (node (ref "U2") (pin "4") (pinfunction "VC_4") (pintype "input+no_connect"))
    )
  )
)
